# 2_-_Power_Protection.net
KiCad netlist of a schematic drawn in Altium Designer
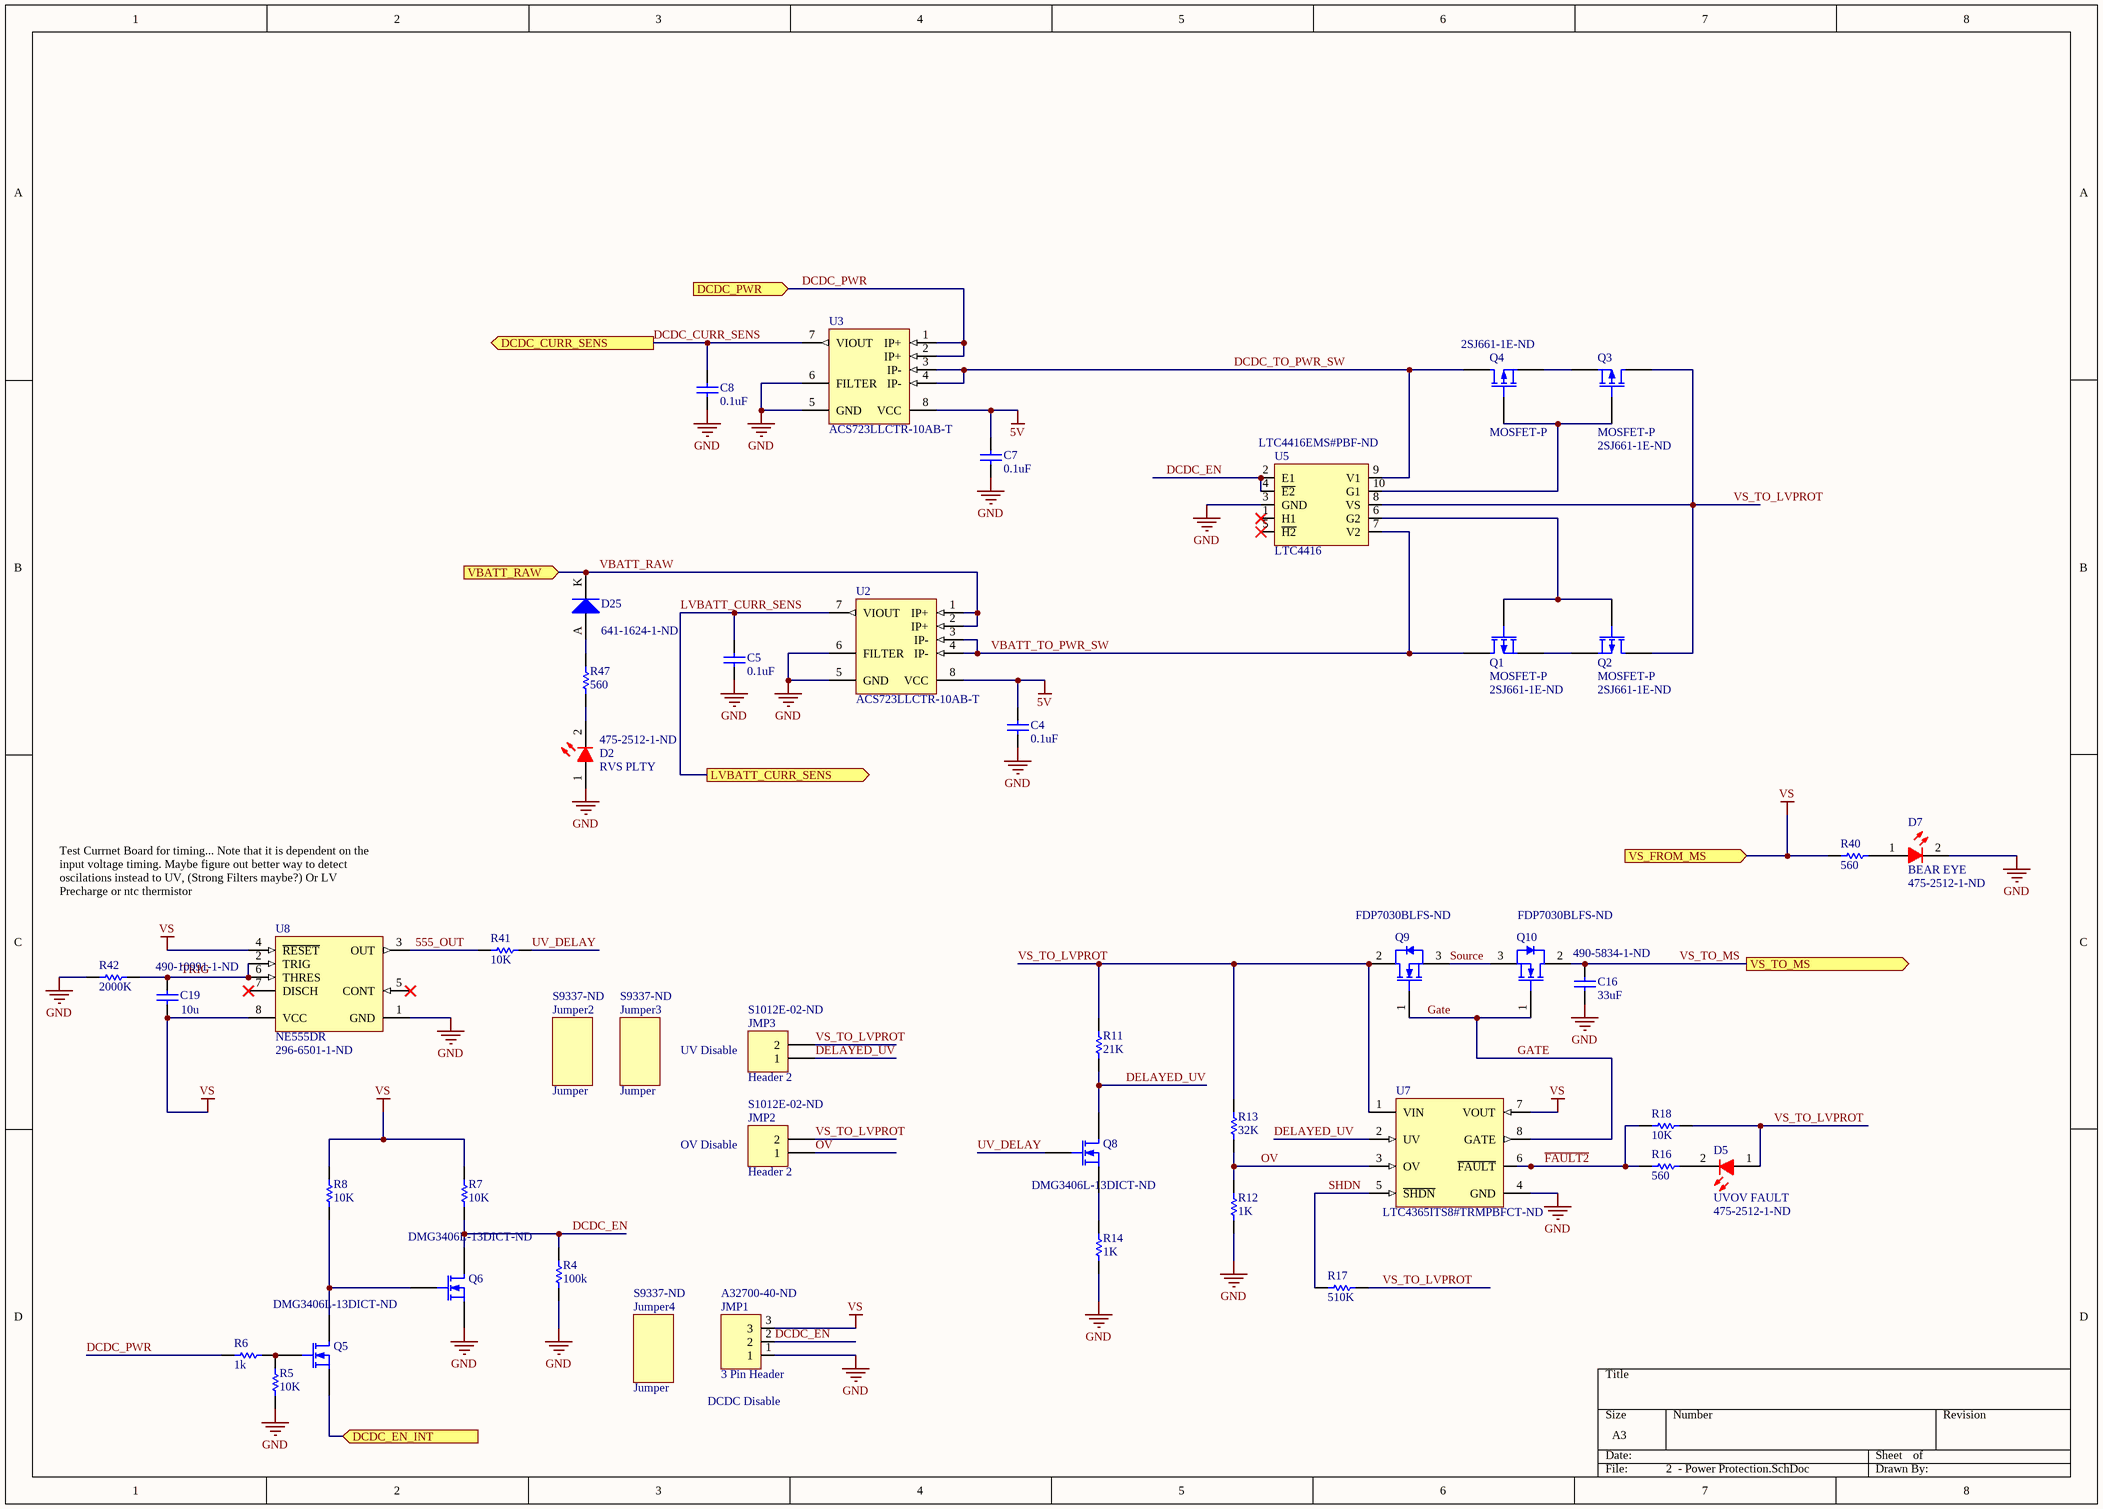
[diagram p0: 2  - Power Protection.SchDoc]

(export (version "E")
  (design (tool "Eeschema 10.0.6"))
  (components
    (comp (ref "C4")
      (value "0.1uF")
      (footprint "1608[0603]")
      (description "Capacitor (Semiconductor SIM Model)")
      (fields (field (name "Comment") "Cap Semi") (field (name "PUBLISHER") "Altium Limited"))
      (libsource (lib "Miscellaneous Devices") (part "Cap Semi"))
    )
    (comp (ref "C5")
      (value "0.1uF")
      (footprint "1608[0603]")
      (description "Capacitor (Semiconductor SIM Model)")
      (fields (field (name "Comment") "Cap Semi") (field (name "PUBLISHER") "Altium Limited"))
      (libsource (lib "Miscellaneous Devices") (part "Cap Semi"))
    )
    (comp (ref "C7")
      (value "0.1uF")
      (footprint "1608[0603]")
      (description "Capacitor (Semiconductor SIM Model)")
      (fields (field (name "Comment") "Cap Semi") (field (name "PUBLISHER") "Altium Limited"))
      (libsource (lib "Miscellaneous Devices") (part "Cap Semi"))
    )
    (comp (ref "C8")
      (value "0.1uF")
      (footprint "1608[0603]")
      (description "Capacitor (Semiconductor SIM Model)")
      (fields (field (name "Comment") "Cap Semi") (field (name "PUBLISHER") "Altium Limited"))
      (libsource (lib "Miscellaneous Devices") (part "Cap Semi"))
    )
    (comp (ref "C16")
      (value "33uF")
      (footprint "2J-Lead 6.1 x 5.3")
      (description "Capacitor (Semiconductor SIM Model)")
      (fields
        (field (name "SUPPLIER PART NUMBER 1") "490-5834-1-ND")
        (field (name "Comment") "Cap Semi")
        (field (name "PUBLISHER") "Altium Limited")
      )
      (libsource (lib "Miscellaneous Devices") (part "Cap Semi"))
    )
    (comp (ref "C19")
      (value "10u")
      (footprint "C1210")
      (description "CAP CER 100UF 6.3V X5R 1206")
      (fields
        (field (name "MANUFACTURER") "Murata Electronics North America")
        (field (name "MANUFACTURER PART NUMBER") "GRM31CR60J107ME39K")
        (field (name "SUPPLIER PART NUMBER 1") "490-10991-1-ND")
      )
      (libsource (lib "Miscellaneous Devices") (part "Cap"))
    )
    (comp (ref "D2")
      (value "RVS PLTY")
      (footprint "TOSH-0603LED_RED_V")
      (description "LED, Red 0603 (1608) 63mCd")
      (fields
        (field (name "MANUFACTURER") "Toshiba")
        (field (name "PARTNUMBER") "TLSU1008A(T04)")
        (field (name "SUPPLIER PART NUMBER 1") "475-2512-1-ND")
      )
      (libsource (lib "Altium Content Vault") (part "CMP-0444-00001-1"))
    )
    (comp (ref "D5")
      (value "UVOV FAULT")
      (footprint "TOSH-0603LED_RED_V")
      (description "LED, Red 0603 (1608) 63mCd")
      (fields
        (field (name "MANUFACTURER") "Toshiba")
        (field (name "PARTNUMBER") "TLSU1008A(T04)")
        (field (name "SUPPLIER PART NUMBER 1") "475-2512-1-ND")
      )
      (libsource (lib "Altium Content Vault") (part "CMP-0444-00001-1"))
    )
    (comp (ref "D7")
      (value "BEAR EYE")
      (footprint "TOSH-0603LED_RED_V")
      (description "LED, Red 0603 (1608) 63mCd")
      (fields
        (field (name "MANUFACTURER") "Toshiba")
        (field (name "PARTNUMBER") "TLSU1008A(T04)")
        (field (name "SUPPLIER PART NUMBER 1") "475-2512-1-ND")
      )
      (libsource (lib "Altium Content Vault") (part "CMP-0444-00001-1"))
    )
    (comp (ref "D25")
      (value "~")
      (footprint "SOD-123")
      (description "1 Amp General Purpose Rectifier")
      (fields
        (field (name "SUPPLIER PART NUMBER 1") "641-1624-1-ND")
        (field (name "PUBLISHER") "Altium Limited")
      )
      (libsource (lib "Miscellaneous Devices") (part "Diode 1N4003"))
    )
    (comp (ref "JMP1")
      (value "3 Pin Header")
      (footprint "3Pin Jumper")
      (fields (field (name "SUPPLIER PART NUMBER 1") "A32700-40-ND"))
      (libsource (lib "ACB_lib") (part "3 Pin Header"))
    )
    (comp (ref "JMP2")
      (value "Header 2")
      (footprint "2Pin Jumper")
      (description "Header, 2-Pin")
      (fields
        (field (name "MANUFACTURER") "Harwin Inc.")
        (field (name "MANUFACTURER PART NUMBER") "M20-9990246")
        (field (name "SUPPLIER PART NUMBER 1") "S1012E-02-ND")
        (field (name "PUBLISHER") "Altium Limited")
      )
      (libsource (lib "Miscellaneous Connectors") (part "Header 2"))
    )
    (comp (ref "JMP3")
      (value "Header 2")
      (footprint "2Pin Jumper")
      (description "Header, 2-Pin")
      (fields
        (field (name "MANUFACTURER") "Harwin Inc.")
        (field (name "MANUFACTURER PART NUMBER") "M20-9990246")
        (field (name "SUPPLIER PART NUMBER 1") "S1012E-02-ND")
        (field (name "PUBLISHER") "Altium Limited")
      )
      (libsource (lib "Miscellaneous Connectors") (part "Header 2"))
    )
    (comp (ref "Jumper2")
      (value "Jumper")
      (fields (field (name "SUPPLIER PART NUMBER 1") "S9337-ND"))
      (libsource (lib "BRAKE TEMP Components") (part "Jumper"))
    )
    (comp (ref "Jumper3")
      (value "Jumper")
      (fields (field (name "SUPPLIER PART NUMBER 1") "S9337-ND"))
      (libsource (lib "BRAKE TEMP Components") (part "Jumper"))
    )
    (comp (ref "Jumper4")
      (value "Jumper")
      (fields (field (name "SUPPLIER PART NUMBER 1") "S9337-ND"))
      (libsource (lib "BRAKE TEMP Components") (part "Jumper"))
    )
    (comp (ref "Q1")
      (value "MOSFET-P")
      (footprint "P-CH Mosfet")
      (description "P-Channel MOSFET  2SJ661-DL-1E")
      (fields
        (field (name "SUPPLIER PART NUMBER 1") "2SJ661-1E-ND")
        (field (name "PUBLISHER") "Altium Limited")
      )
      (libsource (lib "ACB_lib") (part "MOSFET-P"))
    )
    (comp (ref "Q2")
      (value "MOSFET-P")
      (footprint "P-CH Mosfet")
      (description "P-Channel MOSFET  2SJ661-DL-1E")
      (fields
        (field (name "SUPPLIER PART NUMBER 1") "2SJ661-1E-ND")
        (field (name "PUBLISHER") "Altium Limited")
      )
      (libsource (lib "ACB_lib") (part "MOSFET-P"))
    )
    (comp (ref "Q3")
      (value "MOSFET-P")
      (footprint "P-CH Mosfet")
      (description "P-Channel MOSFET  2SJ661-DL-1E")
      (fields
        (field (name "SUPPLIER PART NUMBER 1") "2SJ661-1E-ND")
        (field (name "PUBLISHER") "Altium Limited")
      )
      (libsource (lib "ACB_lib") (part "MOSFET-P"))
    )
    (comp (ref "Q4")
      (value "MOSFET-P")
      (footprint "P-CH Mosfet")
      (description "P-Channel MOSFET  2SJ661-DL-1E")
      (fields
        (field (name "SUPPLIER PART NUMBER 1") "2SJ661-1E-ND")
        (field (name "PUBLISHER") "Altium Limited")
      )
      (libsource (lib "ACB_lib") (part "MOSFET-P"))
    )
    (comp (ref "Q5")
      (value "~")
      (footprint "SOT-23_N")
      (description "N-Channel MOSFET")
      (fields
        (field (name "MANUFACTURER") "Infineon Technologies")
        (field (name "MANUFACTURER PART NUMBER") "IPD075N03L G")
        (field (name "SUPPLIER PART NUMBER 1") "DMG3406L-13DICT-ND")
        (field (name "PUBLISHER") "Altium Limited")
      )
      (libsource (lib "Miscellaneous Devices") (part "MOSFET-N"))
    )
    (comp (ref "Q6")
      (value "~")
      (footprint "SOT-23_N")
      (description "N-Channel MOSFET")
      (fields
        (field (name "MANUFACTURER") "Infineon Technologies")
        (field (name "MANUFACTURER PART NUMBER") "IPD075N03L G")
        (field (name "SUPPLIER PART NUMBER 1") "DMG3406L-13DICT-ND")
        (field (name "PUBLISHER") "Altium Limited")
      )
      (libsource (lib "Miscellaneous Devices") (part "MOSFET-N"))
    )
    (comp (ref "Q8")
      (value "~")
      (footprint "SOT-23_N")
      (description "N-Channel MOSFET")
      (fields
        (field (name "MANUFACTURER") "Infineon Technologies")
        (field (name "MANUFACTURER PART NUMBER") "IPD075N03L G")
        (field (name "SUPPLIER PART NUMBER 1") "DMG3406L-13DICT-ND")
        (field (name "PUBLISHER") "Altium Limited")
      )
      (libsource (lib "Miscellaneous Devices") (part "MOSFET-N"))
    )
    (comp (ref "Q9")
      (value "~")
      (footprint "TO220V-GDS")
      (description "Power MOSFET, 40 V, 167 A, Single N-Channel, 3-Pin TO-220, Pb-Free, Tube")
      (fields (field (name "SUPPLIER PART NUMBER 1") "FDP7030BLFS-ND"))
      (libsource (lib "altium-import") (part "root_1_CMP-1058-00860-1_"))
    )
    (comp (ref "Q10")
      (value "~")
      (footprint "TO220V-GDS")
      (description "Power MOSFET, 40 V, 167 A, Single N-Channel, 3-Pin TO-220, Pb-Free, Tube")
      (fields (field (name "SUPPLIER PART NUMBER 1") "FDP7030BLFS-ND"))
      (libsource (lib "altium-import") (part "root_1_mirrored_CMP-1058-00860-1_"))
    )
    (comp (ref "R4")
      (value "100k")
      (footprint "1608[0603]")
      (description "Resistor")
      (fields
        (field (name "MANUFACTURER") "Rohm Semiconductor")
        (field (name "MANUFACTURER PART NUMBER") "ESR03EZPJ103")
        (field (name "PUBLISHER") "Altium Limited")
      )
      (libsource (lib "Miscellaneous Devices") (part "Res1"))
    )
    (comp (ref "R5")
      (value "10K")
      (footprint "1608[0603]")
      (description "Resistor")
      (fields
        (field (name "MANUFACTURER") "Rohm Semiconductor")
        (field (name "MANUFACTURER PART NUMBER") "ESR03EZPJ103")
        (field (name "PUBLISHER") "Altium Limited")
      )
      (libsource (lib "Miscellaneous Devices") (part "Res1"))
    )
    (comp (ref "R6")
      (value "1k")
      (footprint "1608[0603]")
      (description "Resistor")
      (fields
        (field (name "MANUFACTURER") "Panasonic Electronic Components")
        (field (name "MANUFACTURER PART NUMBER") "ERJ-3EKF60R4V")
        (field (name "PUBLISHER") "Altium Limited")
      )
      (libsource (lib "Miscellaneous Devices") (part "Res1"))
    )
    (comp (ref "R7")
      (value "10K")
      (footprint "1608[0603]")
      (description "Resistor")
      (fields
        (field (name "MANUFACTURER") "Rohm Semiconductor")
        (field (name "MANUFACTURER PART NUMBER") "ESR03EZPJ103")
        (field (name "PUBLISHER") "Altium Limited")
      )
      (libsource (lib "Miscellaneous Devices") (part "Res1"))
    )
    (comp (ref "R8")
      (value "10K")
      (footprint "1608[0603]")
      (description "Resistor")
      (fields
        (field (name "MANUFACTURER") "Rohm Semiconductor")
        (field (name "MANUFACTURER PART NUMBER") "ESR03EZPJ103")
        (field (name "PUBLISHER") "Altium Limited")
      )
      (libsource (lib "Miscellaneous Devices") (part "Res1"))
    )
    (comp (ref "R11")
      (value "21K")
      (footprint "RESC0603(1608)_L")
      (description "0603 (1608 Metric) Chip Resistor")
      (libsource (lib "Altium Content Vault") (part "RES_3"))
    )
    (comp (ref "R12")
      (value "1K")
      (footprint "RESC0603(1608)_L")
      (description "0603 (1608 Metric) Chip Resistor")
      (libsource (lib "Altium Content Vault") (part "RES_3"))
    )
    (comp (ref "R13")
      (value "32K")
      (footprint "RESC0603(1608)_L")
      (description "0603 (1608 Metric) Chip Resistor")
      (libsource (lib "Altium Content Vault") (part "RES_3"))
    )
    (comp (ref "R14")
      (value "1K")
      (footprint "RESC0603(1608)_L")
      (description "0603 (1608 Metric) Chip Resistor")
      (libsource (lib "Altium Content Vault") (part "RES_3"))
    )
    (comp (ref "R16")
      (value "560")
      (footprint "RESC0603(1608)_L")
      (description "0603 (1608 Metric) Chip Resistor")
      (libsource (lib "Altium Content Vault") (part "RES_3"))
    )
    (comp (ref "R17")
      (value "510K")
      (footprint "RESC0603(1608)_L")
      (description "0603 (1608 Metric) Chip Resistor")
      (libsource (lib "Altium Content Vault") (part "RES_3"))
    )
    (comp (ref "R18")
      (value "10K")
      (footprint "RESC0603(1608)_L")
      (description "0603 (1608 Metric) Chip Resistor")
      (libsource (lib "Altium Content Vault") (part "RES_3"))
    )
    (comp (ref "R40")
      (value "560")
      (footprint "RESC0603(1608)_L")
      (description "0603 (1608 Metric) Chip Resistor")
      (libsource (lib "Altium Content Vault") (part "RES_3"))
    )
    (comp (ref "R41")
      (value "10K")
      (footprint "RESC0603(1608)_L")
      (description "0603 (1608 Metric) Chip Resistor")
      (libsource (lib "Altium Content Vault") (part "RES_3"))
    )
    (comp (ref "R42")
      (value "2000K")
      (footprint "RESC0603(1608)_L")
      (description "0603 (1608 Metric) Chip Resistor")
      (libsource (lib "Altium Content Vault") (part "RES_3"))
    )
    (comp (ref "R47")
      (value "560")
      (footprint "RESC0603(1608)_L")
      (description "0603 (1608 Metric) Chip Resistor")
      (libsource (lib "Altium Content Vault") (part "RES_3"))
    )
    (comp (ref "U2")
      (value "ACS723LLCTR-10AB-T")
      (footprint "ALEG-LC-8_V")
      (fields
        (field (name "MANUFACTURER") "Allegro Microsystems")
        (field (name "PARTNUMBER") "ACS712ELCTR-20A-T")
      )
      (libsource (lib "Altium Content Vault") (part "CMP-0826-00001-1"))
    )
    (comp (ref "U3")
      (value "ACS723LLCTR-10AB-T")
      (footprint "ALEG-LC-8_V")
      (fields
        (field (name "MANUFACTURER") "Allegro Microsystems")
        (field (name "PARTNUMBER") "ACS712ELCTR-20A-T")
      )
      (libsource (lib "Altium Content Vault") (part "CMP-0826-00001-1"))
    )
    (comp (ref "U5")
      (value "LTC4416")
      (footprint "LTC4416")
      (description "IC Dual Comparator")
      (fields (field (name "SUPPLIER PART NUMBER 1") "LTC4416EMS#PBF-ND"))
      (libsource (lib "ACB_lib") (part "LTC4416"))
    )
    (comp (ref "U7")
      (value "LTC4365ITS8#TRMPBF")
      (footprint "LT-TS8-8-TSOT-23_V")
      (fields
        (field (name "MANUFACTURER") "Linear Technology")
        (field (name "SUPPLIER PART NUMBER 1") "LTC4365ITS8#TRMPBFCT-ND")
      )
      (libsource (lib "Altium Content Vault") (part "LT-LTC4365-TS8-8"))
    )
    (comp (ref "U8")
      (value "NE555DR")
      (footprint "D0008A_M")
      (fields (field (name "SUPPLIER PART NUMBER 1") "296-6501-1-ND"))
      (libsource (lib "Altium Content Vault") (part "CMP-1685-00007-1"))
    )
  )
  (nets
    (net (code "1") (name "/555_OUT") (class "Default")
      (node (ref "R41") (pin "1") (pinfunction "1_1") (pintype "passive"))
      (node (ref "U8") (pin "3") (pinfunction "OUT_3") (pintype "output"))
    )
    (net (code "2") (name "/DCDC_CURR_SENS") (class "Default")
      (node (ref "C8") (pin "2") (pinfunction "2_2") (pintype "passive"))
      (node (ref "U3") (pin "7") (pinfunction "VIOUT_7") (pintype "output"))
    )
    (net (code "3") (name "/DCDC_EN") (class "Default")
      (node (ref "JMP1") (pin "2") (pinfunction "2_2") (pintype "passive"))
      (node (ref "Q6") (pin "3") (pinfunction "D_3") (pintype "passive"))
      (node (ref "R4") (pin "2") (pinfunction "2_2") (pintype "passive"))
      (node (ref "R7") (pin "1") (pinfunction "1_1") (pintype "passive"))
      (node (ref "U5") (pin "2") (pinfunction "E1_2") (pintype "passive"))
      (node (ref "U5") (pin "4") (pinfunction "~{E2}_4") (pintype "passive"))
    )
    (net (code "4") (name "/DCDC_EN_INT") (class "Default")
      (node (ref "Q5") (pin "2") (pinfunction "S_2") (pintype "passive"))
    )
    (net (code "5") (name "/DCDC_PWR") (class "Default")
      (node (ref "R6") (pin "1") (pinfunction "1_1") (pintype "passive"))
      (node (ref "U3") (pin "1") (pinfunction "IP+_1") (pintype "input"))
      (node (ref "U3") (pin "2") (pinfunction "IP+_2") (pintype "input"))
    )
    (net (code "6") (name "/DCDC_TO_PWR_SW") (class "Default")
      (node (ref "Q4") (pin "2") (pinfunction "D_2") (pintype "passive"))
      (node (ref "U3") (pin "3") (pinfunction "IP-_3") (pintype "input"))
      (node (ref "U3") (pin "4") (pinfunction "IP-_4") (pintype "input"))
      (node (ref "U5") (pin "9") (pinfunction "V1_9") (pintype "passive"))
    )
    (net (code "7") (name "/DELAYED_UV") (class "Default")
      (node (ref "JMP3") (pin "1") (pinfunction "1_1") (pintype "passive"))
      (node (ref "Q8") (pin "3") (pinfunction "D_3") (pintype "passive"))
      (node (ref "R11") (pin "2") (pinfunction "2_2") (pintype "passive"))
      (node (ref "U7") (pin "2") (pinfunction "UV_2") (pintype "input"))
    )
    (net (code "8") (name "/GATE") (class "Default")
      (node (ref "Q10") (pin "1") (pinfunction "G_1") (pintype "passive"))
      (node (ref "Q9") (pin "1") (pinfunction "G_1") (pintype "passive"))
      (node (ref "U7") (pin "8") (pinfunction "GATE_8") (pintype "output"))
    )
    (net (code "9") (name "/LVBATT_CURR_SENS") (class "Default")
      (node (ref "C5") (pin "2") (pinfunction "2_2") (pintype "passive"))
      (node (ref "U2") (pin "7") (pinfunction "VIOUT_7") (pintype "output"))
    )
    (net (code "10") (name "/OV") (class "Default")
      (node (ref "JMP2") (pin "1") (pinfunction "1_1") (pintype "passive"))
      (node (ref "R12") (pin "2") (pinfunction "2_2") (pintype "passive"))
      (node (ref "R13") (pin "1") (pinfunction "1_1") (pintype "passive"))
      (node (ref "U7") (pin "3") (pinfunction "OV_3") (pintype "input"))
    )
    (net (code "11") (name "/SHDN") (class "Default")
      (node (ref "R17") (pin "2") (pinfunction "2_2") (pintype "passive"))
      (node (ref "U7") (pin "5") (pinfunction "~{SHDN}_5") (pintype "input"))
    )
    (net (code "12") (name "/Source") (class "Default")
      (node (ref "Q10") (pin "3") (pinfunction "S_3") (pintype "passive"))
      (node (ref "Q9") (pin "3") (pinfunction "S_3") (pintype "passive"))
    )
    (net (code "13") (name "/TRIG") (class "Default")
      (node (ref "C19") (pin "1") (pinfunction "1_1") (pintype "passive"))
      (node (ref "R42") (pin "1") (pinfunction "1_1") (pintype "passive"))
      (node (ref "U8") (pin "2") (pinfunction "TRIG_2") (pintype "input"))
      (node (ref "U8") (pin "6") (pinfunction "THRES_6") (pintype "input"))
    )
    (net (code "14") (name "/UV_DELAY") (class "Default")
      (node (ref "Q8") (pin "1") (pinfunction "G_1") (pintype "passive"))
      (node (ref "R41") (pin "2") (pinfunction "2_2") (pintype "passive"))
    )
    (net (code "15") (name "/VBATT_RAW") (class "Default")
      (node (ref "D25") (pin "K") (pinfunction "K_K") (pintype "passive"))
      (node (ref "U2") (pin "1") (pinfunction "IP+_1") (pintype "input"))
      (node (ref "U2") (pin "2") (pinfunction "IP+_2") (pintype "input"))
    )
    (net (code "16") (name "/VBATT_TO_PWR_SW") (class "Default")
      (node (ref "Q1") (pin "2") (pinfunction "D_2") (pintype "passive"))
      (node (ref "U2") (pin "3") (pinfunction "IP-_3") (pintype "input"))
      (node (ref "U2") (pin "4") (pinfunction "IP-_4") (pintype "input"))
      (node (ref "U5") (pin "7") (pinfunction "V2_7") (pintype "passive"))
    )
    (net (code "17") (name "/VS_TO_LVPROT") (class "Default")
      (node (ref "D5") (pin "1") (pinfunction "A_1") (pintype "passive"))
      (node (ref "JMP2") (pin "2") (pinfunction "2_2") (pintype "passive"))
      (node (ref "JMP3") (pin "2") (pinfunction "2_2") (pintype "passive"))
      (node (ref "Q2") (pin "2") (pinfunction "D_2") (pintype "passive"))
      (node (ref "Q3") (pin "2") (pinfunction "D_2") (pintype "passive"))
      (node (ref "Q9") (pin "2") (pinfunction "D_2") (pintype "passive"))
      (node (ref "R11") (pin "1") (pinfunction "1_1") (pintype "passive"))
      (node (ref "R13") (pin "2") (pinfunction "2_2") (pintype "passive"))
      (node (ref "R17") (pin "1") (pinfunction "1_1") (pintype "passive"))
      (node (ref "R18") (pin "1") (pinfunction "1_1") (pintype "passive"))
      (node (ref "U5") (pin "8") (pinfunction "VS_8") (pintype "passive"))
      (node (ref "U7") (pin "1") (pinfunction "VIN_1") (pintype "power_in"))
    )
    (net (code "18") (name "/VS_TO_MS") (class "Default")
      (node (ref "C16") (pin "1") (pinfunction "1_1") (pintype "passive"))
      (node (ref "Q10") (pin "2") (pinfunction "D_2") (pintype "passive"))
    )
    (net (code "19") (name "/~{FAULT2}") (class "Default")
      (node (ref "R16") (pin "1") (pinfunction "1_1") (pintype "passive"))
      (node (ref "R18") (pin "2") (pinfunction "2_2") (pintype "passive"))
      (node (ref "U7") (pin "6") (pinfunction "~{FAULT}_6") (pintype "open_collector"))
    )
    (net (code "20") (name "5V") (class "Default")
      (node (ref "C4") (pin "2") (pinfunction "2_2") (pintype "passive"))
      (node (ref "C7") (pin "2") (pinfunction "2_2") (pintype "passive"))
      (node (ref "U2") (pin "8") (pinfunction "VCC_8") (pintype "power_in"))
      (node (ref "U3") (pin "8") (pinfunction "VCC_8") (pintype "power_in"))
    )
    (net (code "21") (name "GND") (class "Default")
      (node (ref "C16") (pin "2") (pinfunction "2_2") (pintype "passive"))
      (node (ref "C4") (pin "1") (pinfunction "1_1") (pintype "passive"))
      (node (ref "C5") (pin "1") (pinfunction "1_1") (pintype "passive"))
      (node (ref "C7") (pin "1") (pinfunction "1_1") (pintype "passive"))
      (node (ref "C8") (pin "1") (pinfunction "1_1") (pintype "passive"))
      (node (ref "D2") (pin "1") (pinfunction "A_1") (pintype "passive"))
      (node (ref "D7") (pin "2") (pinfunction "K_2") (pintype "passive"))
      (node (ref "JMP1") (pin "1") (pinfunction "1_1") (pintype "passive"))
      (node (ref "Q6") (pin "2") (pinfunction "S_2") (pintype "passive"))
      (node (ref "R12") (pin "1") (pinfunction "1_1") (pintype "passive"))
      (node (ref "R14") (pin "2") (pinfunction "2_2") (pintype "passive"))
      (node (ref "R4") (pin "1") (pinfunction "1_1") (pintype "passive"))
      (node (ref "R42") (pin "2") (pinfunction "2_2") (pintype "passive"))
      (node (ref "R5") (pin "1") (pinfunction "1_1") (pintype "passive"))
      (node (ref "U2") (pin "5") (pinfunction "GND_5") (pintype "power_in"))
      (node (ref "U2") (pin "6") (pinfunction "FILTER_6") (pintype "passive"))
      (node (ref "U3") (pin "5") (pinfunction "GND_5") (pintype "power_in"))
      (node (ref "U3") (pin "6") (pinfunction "FILTER_6") (pintype "passive"))
      (node (ref "U5") (pin "3") (pinfunction "GND_3") (pintype "passive"))
      (node (ref "U7") (pin "4") (pinfunction "GND_4") (pintype "power_in"))
      (node (ref "U8") (pin "1") (pinfunction "GND_1") (pintype "power_in"))
    )
    (net (code "22") (name "Net-(D2-K)") (class "Default")
      (node (ref "D2") (pin "2") (pinfunction "K_2") (pintype "passive"))
      (node (ref "R47") (pin "1") (pinfunction "1_1") (pintype "passive"))
    )
    (net (code "23") (name "Net-(D5-K)") (class "Default")
      (node (ref "D5") (pin "2") (pinfunction "K_2") (pintype "passive"))
      (node (ref "R16") (pin "2") (pinfunction "2_2") (pintype "passive"))
    )
    (net (code "24") (name "Net-(D7-A)") (class "Default")
      (node (ref "D7") (pin "1") (pinfunction "A_1") (pintype "passive"))
      (node (ref "R40") (pin "2") (pinfunction "2_2") (pintype "passive"))
    )
    (net (code "25") (name "Net-(D25-PadA)") (class "Default")
      (node (ref "D25") (pin "A") (pinfunction "A_A") (pintype "passive"))
      (node (ref "R47") (pin "2") (pinfunction "2_2") (pintype "passive"))
    )
    (net (code "26") (name "Net-(Q1-G)") (class "Default")
      (node (ref "Q1") (pin "1") (pinfunction "G_1") (pintype "passive"))
      (node (ref "Q2") (pin "1") (pinfunction "G_1") (pintype "passive"))
      (node (ref "U5") (pin "6") (pinfunction "G2_6") (pintype "passive"))
    )
    (net (code "27") (name "Net-(Q1-S)") (class "Default")
      (node (ref "Q1") (pin "3") (pinfunction "S_3") (pintype "passive"))
      (node (ref "Q2") (pin "3") (pinfunction "S_3") (pintype "passive"))
    )
    (net (code "28") (name "Net-(Q3-G)") (class "Default")
      (node (ref "Q3") (pin "1") (pinfunction "G_1") (pintype "passive"))
      (node (ref "Q4") (pin "1") (pinfunction "G_1") (pintype "passive"))
      (node (ref "U5") (pin "10") (pinfunction "G1_10") (pintype "passive"))
    )
    (net (code "29") (name "Net-(Q3-S)") (class "Default")
      (node (ref "Q3") (pin "3") (pinfunction "S_3") (pintype "passive"))
      (node (ref "Q4") (pin "3") (pinfunction "S_3") (pintype "passive"))
    )
    (net (code "30") (name "Net-(Q5-D)") (class "Default")
      (node (ref "Q5") (pin "3") (pinfunction "D_3") (pintype "passive"))
      (node (ref "Q6") (pin "1") (pinfunction "G_1") (pintype "passive"))
      (node (ref "R8") (pin "1") (pinfunction "1_1") (pintype "passive"))
    )
    (net (code "31") (name "Net-(Q5-G)") (class "Default")
      (node (ref "Q5") (pin "1") (pinfunction "G_1") (pintype "passive"))
      (node (ref "R5") (pin "2") (pinfunction "2_2") (pintype "passive"))
      (node (ref "R6") (pin "2") (pinfunction "2_2") (pintype "passive"))
    )
    (net (code "32") (name "Net-(Q8-S)") (class "Default")
      (node (ref "Q8") (pin "2") (pinfunction "S_2") (pintype "passive"))
      (node (ref "R14") (pin "1") (pinfunction "1_1") (pintype "passive"))
    )
    (net (code "33") (name "VS") (class "Default")
      (node (ref "C19") (pin "2") (pinfunction "2_2") (pintype "passive"))
      (node (ref "JMP1") (pin "3") (pinfunction "3_3") (pintype "passive"))
      (node (ref "R40") (pin "1") (pinfunction "1_1") (pintype "passive"))
      (node (ref "R7") (pin "2") (pinfunction "2_2") (pintype "passive"))
      (node (ref "R8") (pin "2") (pinfunction "2_2") (pintype "passive"))
      (node (ref "U7") (pin "7") (pinfunction "VOUT_7") (pintype "input"))
      (node (ref "U8") (pin "4") (pinfunction "~{RESET}_4") (pintype "input"))
      (node (ref "U8") (pin "8") (pinfunction "VCC_8") (pintype "power_in"))
    )
    (net (code "34") (name "unconnected-(U5-H1-Pad1)") (class "Default")
      (node (ref "U5") (pin "1") (pinfunction "H1_1") (pintype "passive+no_connect"))
    )
    (net (code "35") (name "unconnected-(U5-~{H2}-Pad5)") (class "Default")
      (node (ref "U5") (pin "5") (pinfunction "~{H2}_5") (pintype "passive+no_connect"))
    )
    (net (code "36") (name "unconnected-(U8-CONT-Pad5)") (class "Default")
      (node (ref "U8") (pin "5") (pinfunction "CONT_5") (pintype "input+no_connect"))
    )
    (net (code "37") (name "unconnected-(U8-DISCH-Pad7)") (class "Default")
      (node (ref "U8") (pin "7") (pinfunction "DISCH_7") (pintype "open_collector+no_connect"))
    )
  )
)
